# TopSheet.net
KiCad netlist of a schematic drawn in Altium Designer
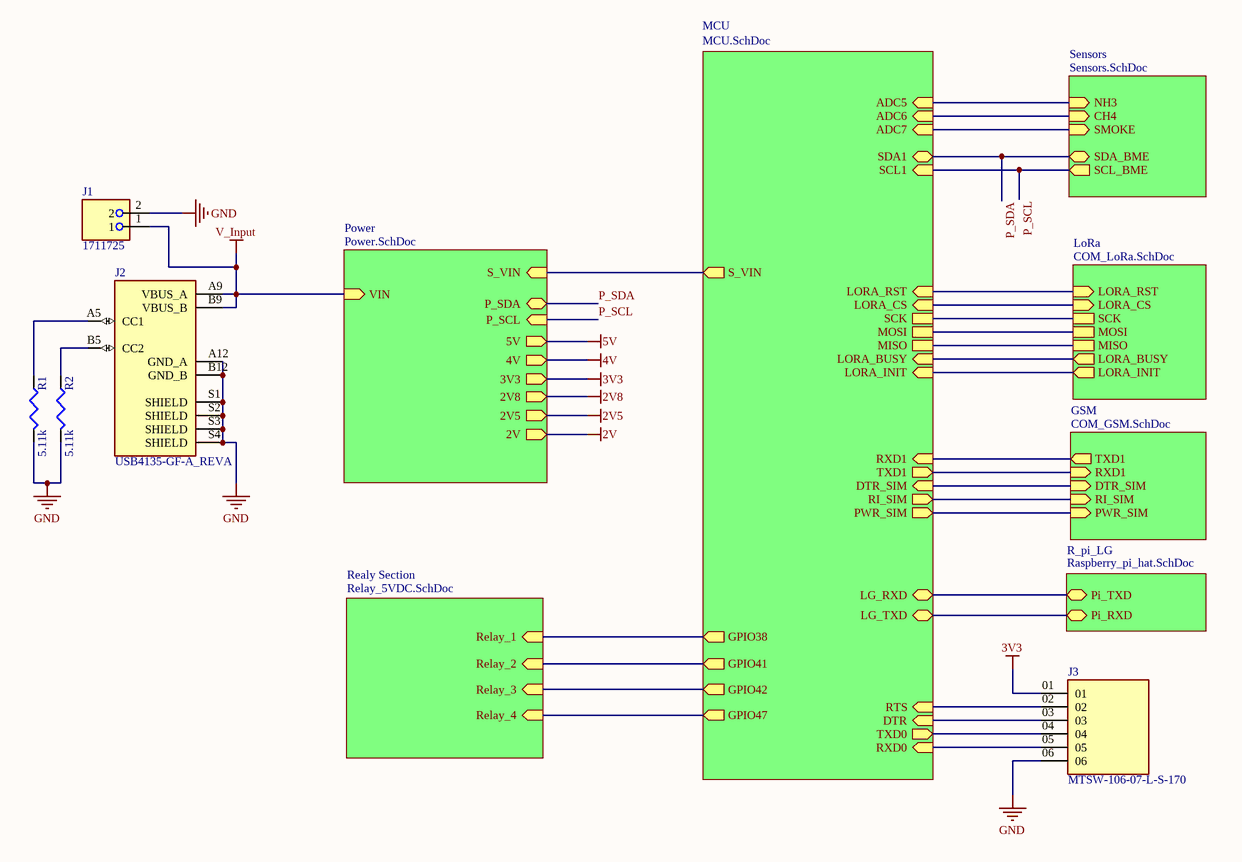
[diagram p0: TopSheet.SchDoc]

(export (version "E")
  (design (tool "Eeschema 10.0.6"))
  (components
    (comp (ref "J1")
      (value "1711725")
      (footprint "PHOENIX_1711725")
      (description "PCB Terminal Screw 5.08mm 12AWG 400V 24A 2 Position COMBICON MKDS Series ¦ Phoenix Contact 1711725")
      (fields (field (name "MF") "Phoenix Contact"))
      (libsource (lib "1711725") (part "1711725"))
    )
    (comp (ref "J2")
      (value "USB4135-GF-A_REVA")
      (footprint "GCT_USB4135-GF-A_REVA")
      (description "Type C Receptacle, Horizontal, SMT, For Power Charging Only")
      (fields (field (name "MP") "USB4135-GF-A") (field (name "MF") "Global Connector Technology"))
      (libsource (lib "Type-c") (part "USB4135-GF-A_REVA"))
    )
    (comp (ref "J3")
      (value "MTSW-106-07-L-S-170")
      (footprint "SAMTEC_MTSW-106-07-L-S-170")
      (libsource (lib "MTSW-106-07-L-S-170") (part "MTSW-106-07-L-S-170"))
    )
    (comp (ref "R1")
      (value "5.11k")
      (footprint "R0603")
      (libsource (lib "common component") (part "Resistor"))
    )
    (comp (ref "R2")
      (value "5.11k")
      (footprint "R0603")
      (libsource (lib "common component") (part "Resistor"))
    )
  )
  (nets
    (net (code "4") (name "/DTR") (class "Default")
      (node (ref "J3") (pin "03") (pinfunction "03_03") (pintype "passive"))
    )
    (net (code "22") (name "/RTS") (class "Default")
      (node (ref "J3") (pin "02") (pinfunction "02_02") (pintype "passive"))
    )
    (net (code "23") (name "/RXD0") (class "Default")
      (node (ref "J3") (pin "05") (pinfunction "05_05") (pintype "passive"))
    )
    (net (code "26") (name "/TXD0") (class "Default")
      (node (ref "J3") (pin "04") (pinfunction "04_04") (pintype "passive"))
    )
    (net (code "32") (name "3V3") (class "Default")
      (node (ref "J3") (pin "01") (pinfunction "01_01") (pintype "passive"))
    )
    (net (code "35") (name "GND") (class "Default")
      (node (ref "J1") (pin "2") (pinfunction "2_2") (pintype "passive"))
      (node (ref "J2") (pin "A12") (pinfunction "GND_A_A12") (pintype "power_in"))
      (node (ref "J2") (pin "B12") (pinfunction "GND_B_B12") (pintype "power_in"))
      (node (ref "J2") (pin "S1") (pinfunction "SHIELD_S1") (pintype "passive"))
      (node (ref "J2") (pin "S2") (pinfunction "SHIELD_S2") (pintype "passive"))
      (node (ref "J2") (pin "S3") (pinfunction "SHIELD_S3") (pintype "passive"))
      (node (ref "J2") (pin "S4") (pinfunction "SHIELD_S4") (pintype "passive"))
      (node (ref "J3") (pin "06") (pinfunction "06_06") (pintype "passive"))
      (node (ref "R1") (pin "2") (pinfunction "2_2") (pintype "passive"))
      (node (ref "R2") (pin "2") (pinfunction "2_2") (pintype "passive"))
    )
    (net (code "36") (name "Net-(J2-CC1)") (class "Default")
      (node (ref "J2") (pin "A5") (pinfunction "CC1_A5") (pintype "bidirectional"))
      (node (ref "R1") (pin "1") (pinfunction "1_1") (pintype "passive"))
    )
    (net (code "37") (name "Net-(J2-CC2)") (class "Default")
      (node (ref "J2") (pin "B5") (pinfunction "CC2_B5") (pintype "bidirectional"))
      (node (ref "R2") (pin "1") (pinfunction "1_1") (pintype "passive"))
    )
    (net (code "38") (name "V_Input") (class "Default")
      (node (ref "J1") (pin "1") (pinfunction "1_1") (pintype "passive"))
      (node (ref "J2") (pin "A9") (pinfunction "VBUS_A_A9") (pintype "power_in"))
      (node (ref "J2") (pin "B9") (pinfunction "VBUS_B_B9") (pintype "power_in"))
    )
  )
)
